# LD_driver.net
KiCad netlist of a schematic drawn in Altium Designer
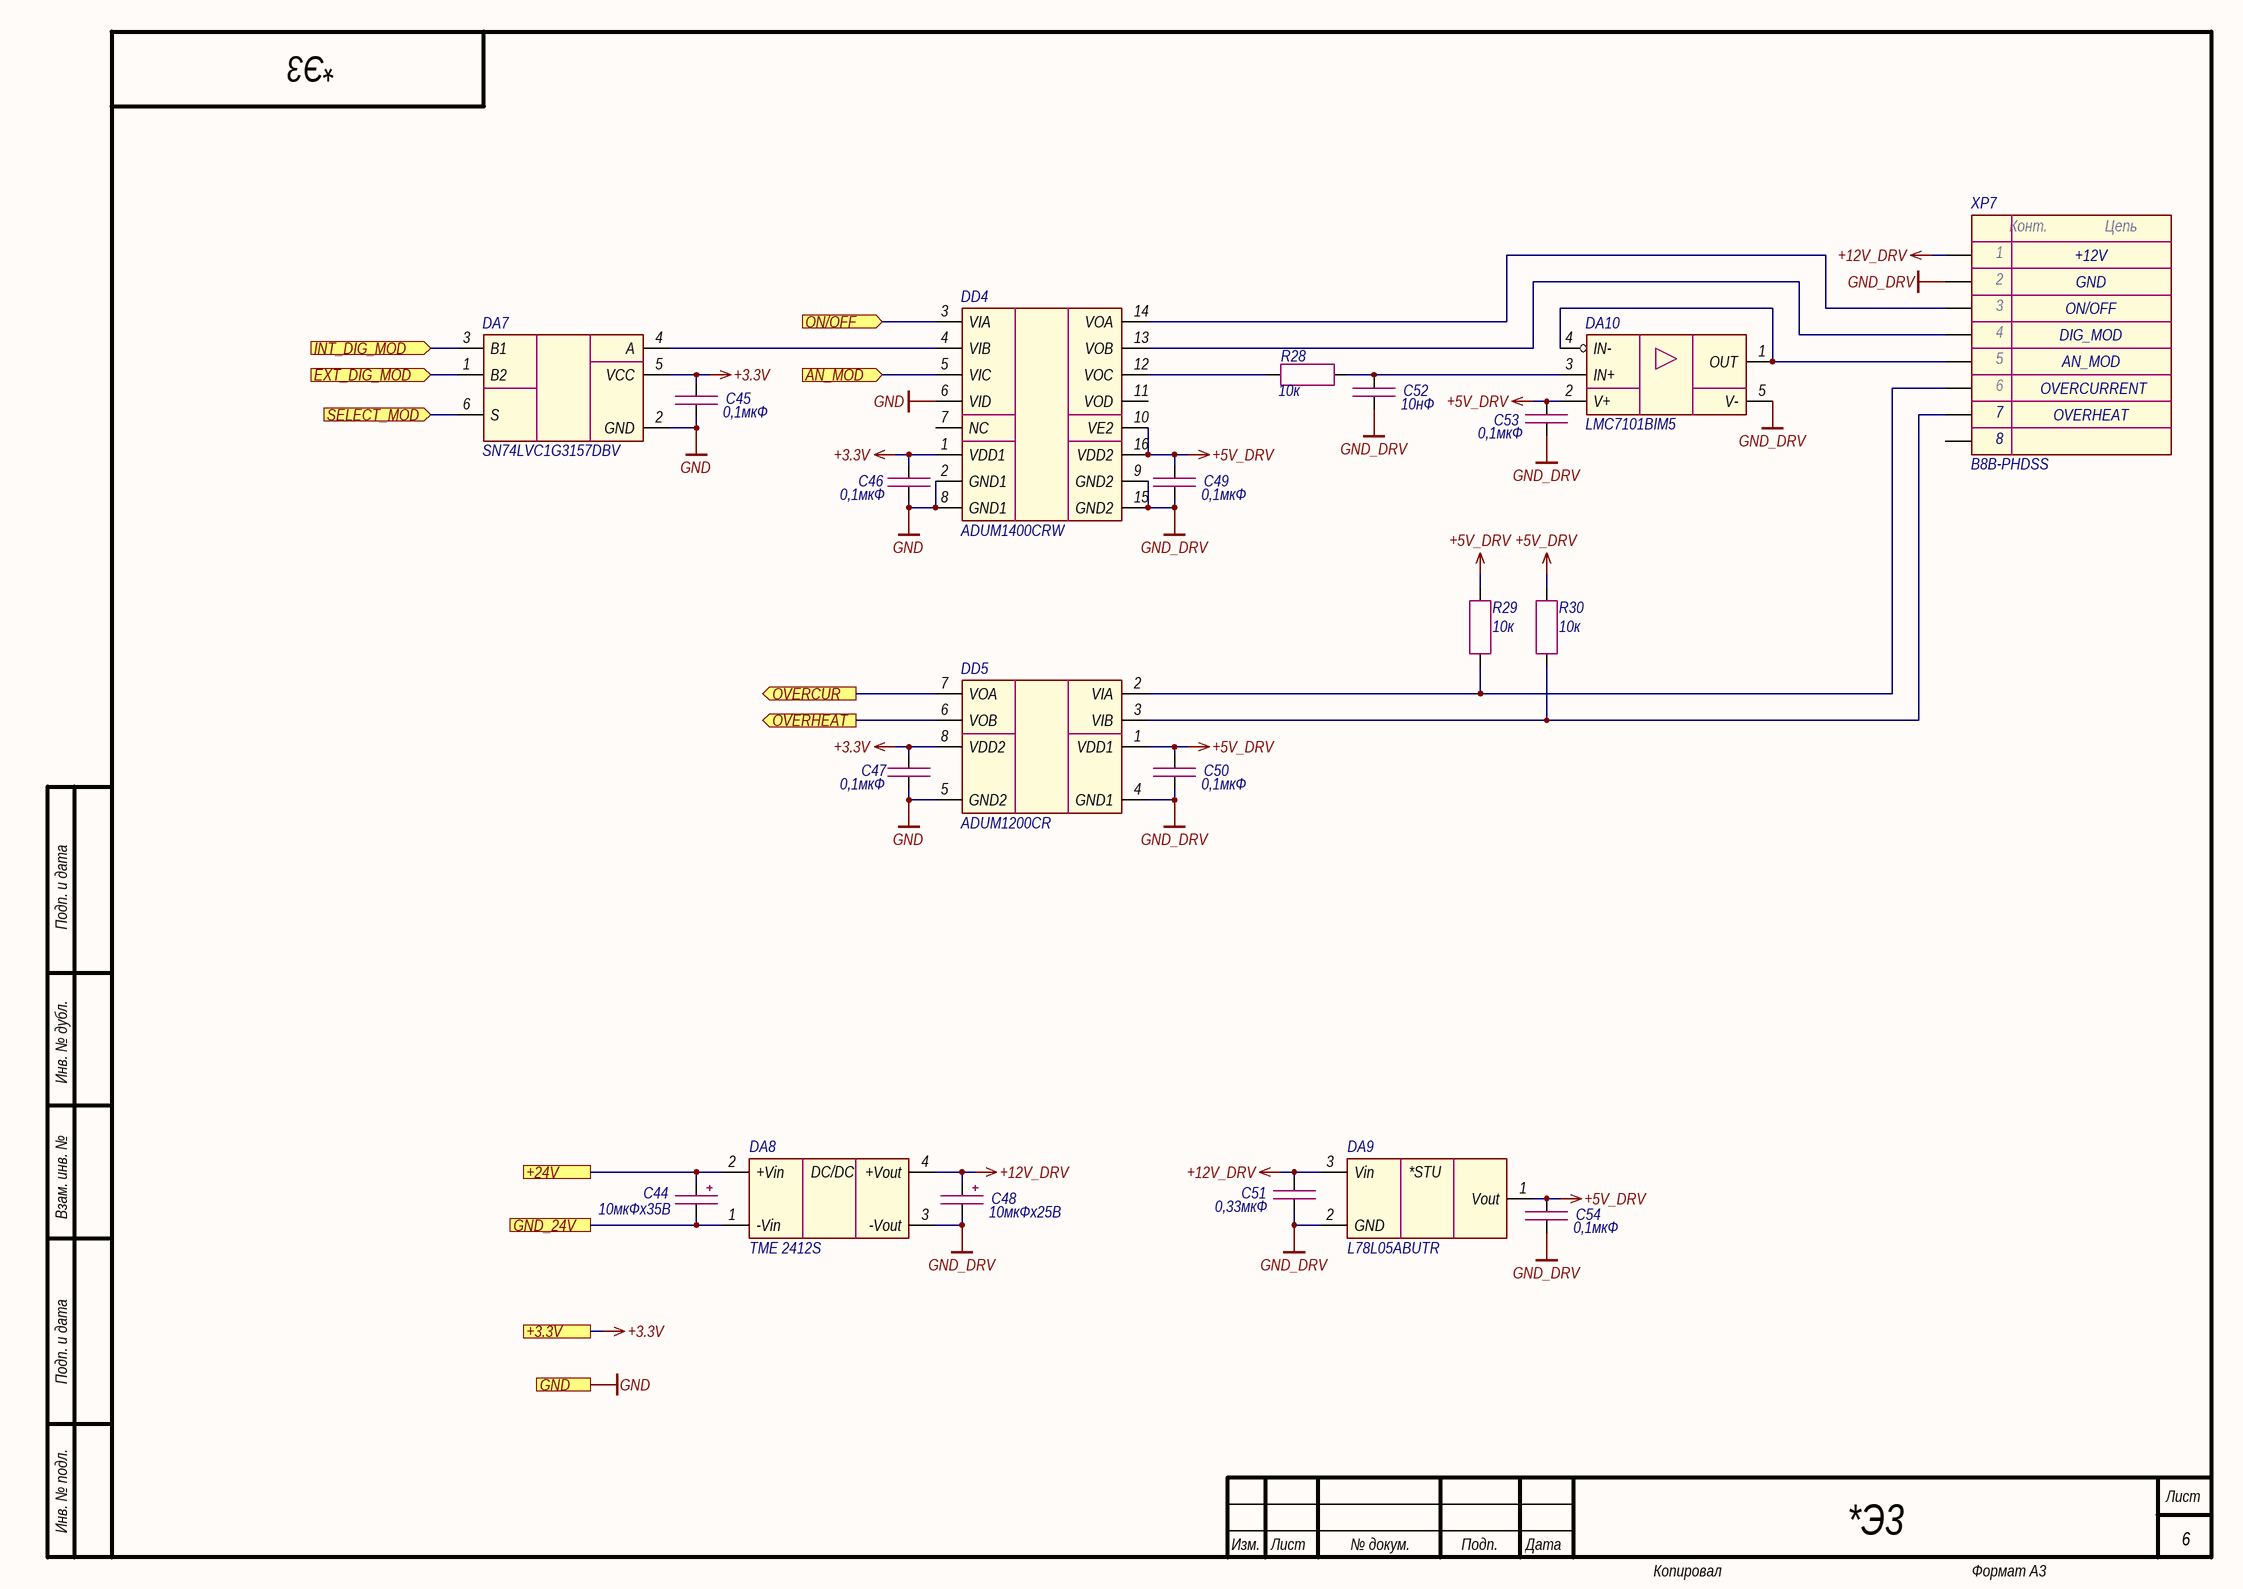
[diagram p0: LD_driver.SchDoc]

(export (version "E")
  (design (tool "Eeschema 10.0.6"))
  (components
    (comp (ref "C44")
      (value "10мкФх35B")
      (footprint "Pcb_library:CAP_C")
      (libsource (lib "Schem_library") (part "Capacitor_Polar"))
    )
    (comp (ref "C45")
      (value "0,1мкФ")
      (footprint "Pcb_library:CAP_0603")
      (fields (field (name "MANUFACTURER") "Murata"))
      (libsource (lib "Schem_library") (part "Capacitor"))
    )
    (comp (ref "C46")
      (value "0,1мкФ")
      (footprint "Pcb_library:CAP_0603")
      (fields (field (name "MANUFACTURER") "Murata"))
      (libsource (lib "Schem_library") (part "Capacitor"))
    )
    (comp (ref "C47")
      (value "0,1мкФ")
      (footprint "Pcb_library:CAP_0603")
      (fields (field (name "MANUFACTURER") "Murata"))
      (libsource (lib "Schem_library") (part "Capacitor"))
    )
    (comp (ref "C48")
      (value "10мкФх25B")
      (footprint "Pcb_library:CAP_B")
      (libsource (lib "Schem_library") (part "Capacitor_Polar"))
    )
    (comp (ref "C49")
      (value "0,1мкФ")
      (footprint "Pcb_library:CAP_0603")
      (fields (field (name "MANUFACTURER") "Murata"))
      (libsource (lib "Schem_library") (part "Capacitor"))
    )
    (comp (ref "C50")
      (value "0,1мкФ")
      (footprint "Pcb_library:CAP_0603")
      (fields (field (name "MANUFACTURER") "Murata"))
      (libsource (lib "Schem_library") (part "Capacitor"))
    )
    (comp (ref "C51")
      (value "0,33мкФ")
      (footprint "Pcb_library:CAP_0805")
      (fields (field (name "MANUFACTURER") "Murata"))
      (libsource (lib "Schem_library") (part "Capacitor"))
    )
    (comp (ref "C52")
      (value "10нФ")
      (footprint "Pcb_library:CAP_0603")
      (fields (field (name "MANUFACTURER") "Murata"))
      (libsource (lib "Schem_library") (part "Capacitor"))
    )
    (comp (ref "C53")
      (value "0,1мкФ")
      (footprint "Pcb_library:CAP_0603")
      (fields (field (name "MANUFACTURER") "Murata"))
      (libsource (lib "Schem_library") (part "Capacitor"))
    )
    (comp (ref "C54")
      (value "0,1мкФ")
      (footprint "Pcb_library:CAP_0603")
      (fields (field (name "MANUFACTURER") "Murata"))
      (libsource (lib "Schem_library") (part "Capacitor"))
    )
    (comp (ref "DA7")
      (value "SN74LVC1G3157DBV")
      (footprint "Pcb_library:SOT-23-6")
      (fields (field (name "MANUFACTURER") "Texas Instruments"))
      (libsource (lib "Schem_library") (part "SN74LVC1G3157"))
    )
    (comp (ref "DA8")
      (value "TME 2412S")
      (footprint "Pcb_library:TME (SIP-4)")
      (fields (field (name "MANUFACTURER") "Traco Power"))
      (libsource (lib "Schem_library") (part "TME"))
    )
    (comp (ref "DA9")
      (value "L78L05ABUTR")
      (footprint "Pcb_library:SOT-89")
      (fields (field (name "MANUFACTURER") "STMicroelectronics"))
      (libsource (lib "Schem_library") (part "LD2981ABU50TR"))
    )
    (comp (ref "DA10")
      (value "LMC7101BIM5")
      (footprint "Pcb_library:SOT-23-5")
      (fields (field (name "MANUFACTURER") "Texas Instruments"))
      (libsource (lib "Schem_library") (part "LMC7101"))
    )
    (comp (ref "DD4")
      (value "ADUM1400CRW")
      (footprint "Pcb_library:SOIC-16W")
      (fields (field (name "MANUFACTURER") "Analog Devices"))
      (libsource (lib "Schem_library") (part "ADUM1400"))
    )
    (comp (ref "DD5")
      (value "ADUM1200CR")
      (footprint "Pcb_library:SOIC-8")
      (fields (field (name "MANUFACTURER") "Analog Devices"))
      (libsource (lib "Schem_library") (part "ADUM1200"))
    )
    (comp (ref "R28")
      (value "10к")
      (footprint "Pcb_library:RES_0603")
      (fields (field (name "MANUFACTURER") "Yageo"))
      (libsource (lib "Schem_library") (part "Resistor"))
    )
    (comp (ref "R29")
      (value "10к")
      (footprint "Pcb_library:RES_0603")
      (fields (field (name "MANUFACTURER") "Yageo"))
      (libsource (lib "Schem_library") (part "Resistor"))
    )
    (comp (ref "R30")
      (value "10к")
      (footprint "Pcb_library:RES_0603")
      (fields (field (name "MANUFACTURER") "Yageo"))
      (libsource (lib "Schem_library") (part "Resistor"))
    )
    (comp (ref "XP7")
      (value "B8B-PHDSS")
      (footprint "Pcb_library:B8B-PHDSS")
      (fields (field (name "MANUFACTURER") "JST"))
      (libsource (lib "Schem_library") (part "Connector-8"))
    )
  )
  (nets
    (net (code "1") (name "+3.3V") (class "Default")
      (node (ref "C45") (pin "1") (pinfunction "1_1") (pintype "passive"))
      (node (ref "C46") (pin "1") (pinfunction "1_1") (pintype "passive"))
      (node (ref "C47") (pin "1") (pinfunction "1_1") (pintype "passive"))
      (node (ref "DA7") (pin "5") (pinfunction "VCC_5") (pintype "passive"))
      (node (ref "DD4") (pin "1") (pinfunction "VDD1_1") (pintype "passive"))
      (node (ref "DD5") (pin "8") (pinfunction "VDD2_8") (pintype "passive"))
    )
    (net (code "2") (name "+5V_DRV") (class "Default")
      (node (ref "C49") (pin "1") (pinfunction "1_1") (pintype "passive"))
      (node (ref "C50") (pin "1") (pinfunction "1_1") (pintype "passive"))
      (node (ref "C53") (pin "1") (pinfunction "1_1") (pintype "passive"))
      (node (ref "C54") (pin "1") (pinfunction "1_1") (pintype "passive"))
      (node (ref "DA10") (pin "2") (pinfunction "V+_2") (pintype "passive"))
      (node (ref "DA9") (pin "1") (pinfunction "Vout_1") (pintype "passive"))
      (node (ref "DD4") (pin "10") (pinfunction "VE2_10") (pintype "passive"))
      (node (ref "DD4") (pin "16") (pinfunction "VDD2_16") (pintype "passive"))
      (node (ref "DD5") (pin "1") (pinfunction "VDD1_1") (pintype "passive"))
      (node (ref "R29") (pin "1") (pinfunction "1_1") (pintype "passive"))
      (node (ref "R30") (pin "1") (pinfunction "1_1") (pintype "passive"))
    )
    (net (code "3") (name "+12V_DRV") (class "Default")
      (node (ref "C48") (pin "1") (pinfunction "1_1") (pintype "passive"))
      (node (ref "C51") (pin "2") (pinfunction "2_2") (pintype "passive"))
      (node (ref "DA8") (pin "4") (pinfunction "+Vout_4") (pintype "passive"))
      (node (ref "DA9") (pin "3") (pinfunction "Vin_3") (pintype "passive"))
      (node (ref "XP7") (pin "1") (pintype "passive"))
    )
    (net (code "4") (name "/+24V") (class "Default")
      (node (ref "C44") (pin "1") (pinfunction "1_1") (pintype "passive"))
      (node (ref "DA8") (pin "2") (pinfunction "+Vin_2") (pintype "passive"))
    )
    (net (code "5") (name "/AN_MOD") (class "Default")
      (node (ref "DD4") (pin "5") (pinfunction "VIC_5") (pintype "passive"))
    )
    (net (code "6") (name "/EXT_DIG_MOD") (class "Default")
      (node (ref "DA7") (pin "1") (pinfunction "B2_1") (pintype "passive"))
    )
    (net (code "7") (name "/GND_24V") (class "Default")
      (node (ref "C44") (pin "2") (pinfunction "2_2") (pintype "passive"))
      (node (ref "DA8") (pin "1") (pinfunction "-Vin_1") (pintype "passive"))
    )
    (net (code "8") (name "/INT_DIG_MOD") (class "Default")
      (node (ref "DA7") (pin "3") (pinfunction "B1_3") (pintype "passive"))
    )
    (net (code "9") (name "/ON{slash}OFF") (class "Default")
      (node (ref "DD4") (pin "3") (pinfunction "VIA_3") (pintype "passive"))
    )
    (net (code "10") (name "/OVERCUR") (class "Default")
      (node (ref "DD5") (pin "7") (pinfunction "VOA_7") (pintype "passive"))
    )
    (net (code "11") (name "/OVERHEAT") (class "Default")
      (node (ref "DD5") (pin "6") (pinfunction "VOB_6") (pintype "passive"))
    )
    (net (code "12") (name "/SELECT_MOD") (class "Default")
      (node (ref "DA7") (pin "6") (pinfunction "S_6") (pintype "passive"))
    )
    (net (code "13") (name "GND") (class "Default")
      (node (ref "C45") (pin "2") (pinfunction "2_2") (pintype "passive"))
      (node (ref "C46") (pin "2") (pinfunction "2_2") (pintype "passive"))
      (node (ref "C47") (pin "2") (pinfunction "2_2") (pintype "passive"))
      (node (ref "DA7") (pin "2") (pinfunction "GND_2") (pintype "passive"))
      (node (ref "DD4") (pin "2") (pinfunction "GND1_2") (pintype "passive"))
      (node (ref "DD4") (pin "6") (pinfunction "VID_6") (pintype "passive"))
      (node (ref "DD4") (pin "8") (pinfunction "GND1_8") (pintype "passive"))
      (node (ref "DD5") (pin "5") (pinfunction "GND2_5") (pintype "passive"))
    )
    (net (code "14") (name "GND_DRV") (class "Default")
      (node (ref "C48") (pin "2") (pinfunction "2_2") (pintype "passive"))
      (node (ref "C49") (pin "2") (pinfunction "2_2") (pintype "passive"))
      (node (ref "C50") (pin "2") (pinfunction "2_2") (pintype "passive"))
      (node (ref "C51") (pin "1") (pinfunction "1_1") (pintype "passive"))
      (node (ref "C52") (pin "2") (pinfunction "2_2") (pintype "passive"))
      (node (ref "C53") (pin "2") (pinfunction "2_2") (pintype "passive"))
      (node (ref "C54") (pin "2") (pinfunction "2_2") (pintype "passive"))
      (node (ref "DA10") (pin "5") (pinfunction "V-_5") (pintype "passive"))
      (node (ref "DA8") (pin "3") (pinfunction "-Vout_3") (pintype "passive"))
      (node (ref "DA9") (pin "2") (pinfunction "GND_2") (pintype "passive"))
      (node (ref "DD4") (pin "15") (pinfunction "GND2_15") (pintype "passive"))
      (node (ref "DD4") (pin "9") (pinfunction "GND2_9") (pintype "passive"))
      (node (ref "DD5") (pin "4") (pinfunction "GND1_4") (pintype "passive"))
      (node (ref "XP7") (pin "2") (pintype "passive"))
    )
    (net (code "15") (name "Net-(DA7-A)") (class "Default")
      (node (ref "DA7") (pin "4") (pinfunction "A_4") (pintype "passive"))
      (node (ref "DD4") (pin "4") (pinfunction "VIB_4") (pintype "passive"))
    )
    (net (code "16") (name "Net-(DA10-IN+)") (class "Default")
      (node (ref "C52") (pin "1") (pinfunction "1_1") (pintype "passive"))
      (node (ref "DA10") (pin "3") (pinfunction "IN+_3") (pintype "passive"))
      (node (ref "R28") (pin "2") (pinfunction "2_2") (pintype "passive"))
    )
    (net (code "17") (name "Net-(DA10-IN-)") (class "Default")
      (node (ref "DA10") (pin "1") (pinfunction "OUT_1") (pintype "passive"))
      (node (ref "DA10") (pin "4") (pinfunction "IN-_4") (pintype "passive"))
      (node (ref "XP7") (pin "5") (pintype "passive"))
    )
    (net (code "18") (name "Net-(DD4-VOA)") (class "Default")
      (node (ref "DD4") (pin "14") (pinfunction "VOA_14") (pintype "passive"))
      (node (ref "XP7") (pin "3") (pintype "passive"))
    )
    (net (code "19") (name "Net-(DD4-VOB)") (class "Default")
      (node (ref "DD4") (pin "13") (pinfunction "VOB_13") (pintype "passive"))
      (node (ref "XP7") (pin "4") (pintype "passive"))
    )
    (net (code "20") (name "Net-(DD4-VOC)") (class "Default")
      (node (ref "DD4") (pin "12") (pinfunction "VOC_12") (pintype "passive"))
      (node (ref "R28") (pin "1") (pinfunction "1_1") (pintype "passive"))
    )
    (net (code "21") (name "Net-(DD5-VIA)") (class "Default")
      (node (ref "DD5") (pin "2") (pinfunction "VIA_2") (pintype "passive"))
      (node (ref "R29") (pin "2") (pinfunction "2_2") (pintype "passive"))
      (node (ref "XP7") (pin "6") (pintype "passive"))
    )
    (net (code "22") (name "Net-(DD5-VIB)") (class "Default")
      (node (ref "DD5") (pin "3") (pinfunction "VIB_3") (pintype "passive"))
      (node (ref "R30") (pin "2") (pinfunction "2_2") (pintype "passive"))
      (node (ref "XP7") (pin "7") (pintype "passive"))
    )
    (net (code "23") (name "unconnected-(DD4-NC-Pad7)") (class "Default")
      (node (ref "DD4") (pin "7") (pinfunction "NC_7") (pintype "passive"))
    )
    (net (code "24") (name "unconnected-(DD4-VOD-Pad11)") (class "Default")
      (node (ref "DD4") (pin "11") (pinfunction "VOD_11") (pintype "passive"))
    )
    (net (code "25") (name "unconnected-(XP7-Pad8)") (class "Default")
      (node (ref "XP7") (pin "8") (pintype "passive"))
    )
  )
)
